# Power.net
KiCad netlist of a schematic drawn in Altium Designer
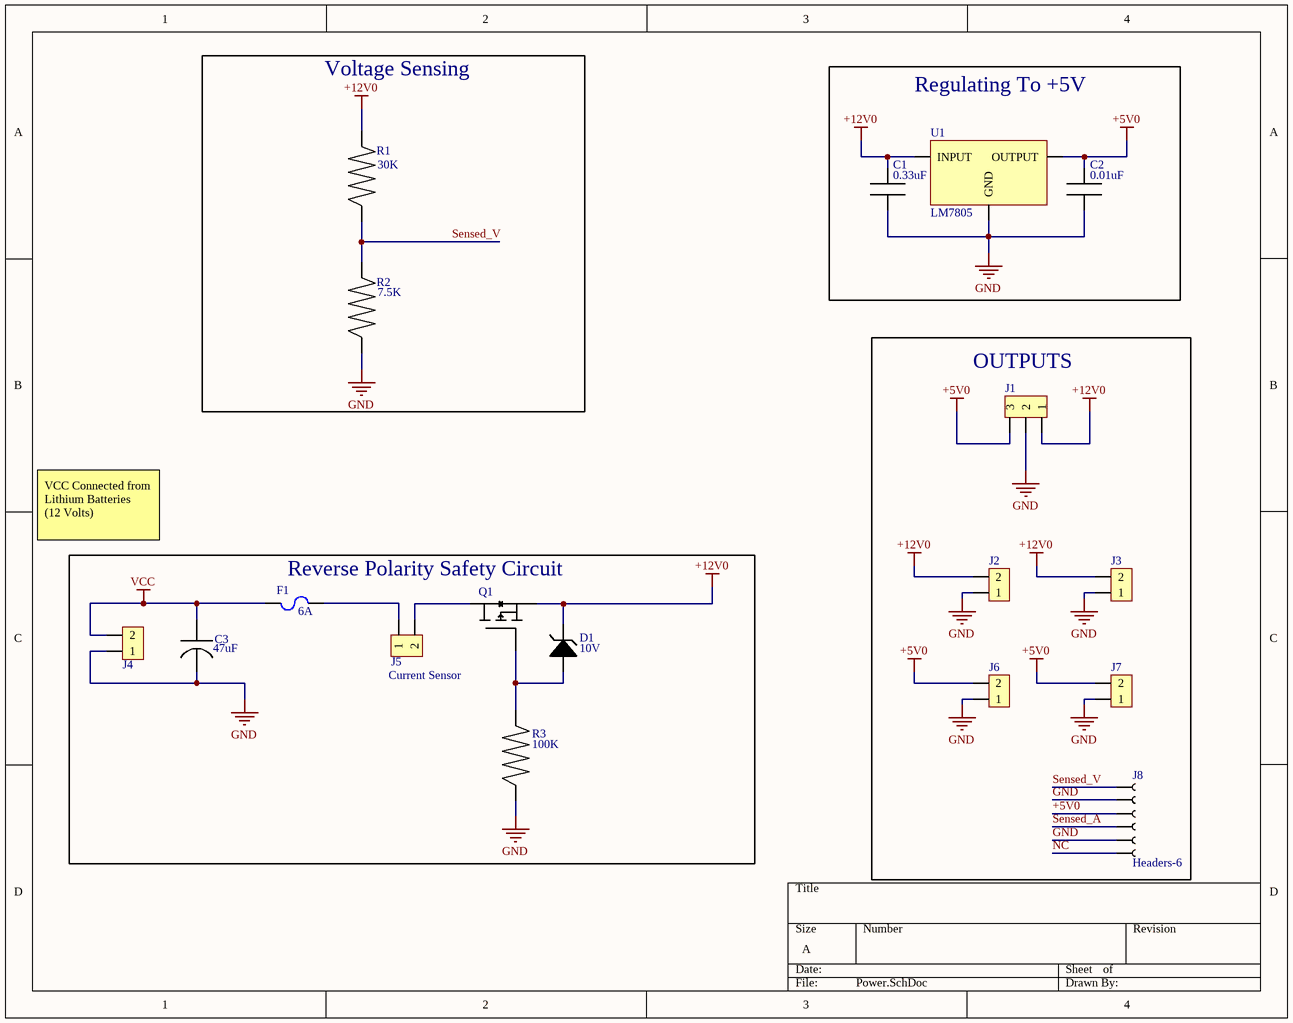
[diagram p0: Power.SchDoc]

(export (version "E")
  (design (tool "Eeschema 10.0.6"))
  (components
    (comp (ref "C1")
      (value "0.33uF")
      (footprint "Ceramic Cap")
      (fields (field (name "Comment") "Ceramic Capacitor"))
      (libsource (lib "Components") (part "Ceramic Capacitor"))
    )
    (comp (ref "C2")
      (value "0.01uF")
      (footprint "Ceramic Cap")
      (fields (field (name "Comment") "Ceramic Capacitor"))
      (libsource (lib "Components") (part "Ceramic Capacitor"))
    )
    (comp (ref "C3")
      (value "47uF")
      (footprint "ALCap.")
      (fields (field (name "Comment") "ALCapacitor"))
      (libsource (lib "Components") (part "ALCapacitor"))
    )
    (comp (ref "D1")
      (value "Zener")
      (footprint "Zener10")
      (fields (field (name "VD") "10V"))
      (libsource (lib "Components") (part "Zener"))
    )
    (comp (ref "F1")
      (value "6A")
      (footprint "Fuse Base")
      (fields (field (name "Comment") "Fuse"))
      (libsource (lib "Components") (part "Fuse"))
    )
    (comp (ref "J1")
      (value "Terminal Block 3")
      (footprint "Terminal Block 3")
      (libsource (lib "Components") (part "Terminal Block 3"))
    )
    (comp (ref "J2")
      (value "Terminal Block 2-pins")
      (footprint "Terminal Block 2 Plugable")
      (fields (field (name "MF") "Phoenix Contact"))
      (libsource (lib "Components") (part "Terminal Block 2-pins"))
    )
    (comp (ref "J3")
      (value "Terminal Block 2-pins")
      (footprint "Terminal Block 2 Plugable")
      (fields (field (name "MF") "Phoenix Contact"))
      (libsource (lib "Components") (part "Terminal Block 2-pins"))
    )
    (comp (ref "J4")
      (value "Terminal Block 2-pins")
      (footprint "Terminal Block 2 Plugable")
      (fields (field (name "MF") "Phoenix Contact"))
      (libsource (lib "Components") (part "Terminal Block 2-pins"))
    )
    (comp (ref "J5")
      (value "Current Sensor")
      (footprint "Terminal Block 2 Plugable")
      (fields (field (name "MF") "Phoenix Contact"))
      (libsource (lib "") (part "Terminal Block 2-pins_1"))
    )
    (comp (ref "J6")
      (value "Terminal Block 2-pins")
      (footprint "Terminal Block 2 Plugable")
      (fields (field (name "MF") "Phoenix Contact"))
      (libsource (lib "Components") (part "Terminal Block 2-pins"))
    )
    (comp (ref "J7")
      (value "Terminal Block 2-pins")
      (footprint "Terminal Block 2 Plugable")
      (fields (field (name "MF") "Phoenix Contact"))
      (libsource (lib "Components") (part "Terminal Block 2-pins"))
    )
    (comp (ref "J8")
      (value "Headers-6")
      (footprint "Headers 6-pins")
      (libsource (lib "Components") (part "Headers-6"))
    )
    (comp (ref "Q1")
      (value "MOSFET")
      (footprint "IRF9540")
      (description "P-Channel")
      (libsource (lib "Components") (part "MOSFET"))
    )
    (comp (ref "R1")
      (value "30K")
      (footprint "resistor")
      (fields (field (name "Comment") "Resistor"))
      (libsource (lib "Components") (part "Resistor"))
    )
    (comp (ref "R2")
      (value "7.5K")
      (footprint "resistor")
      (fields (field (name "Comment") "Resistor"))
      (libsource (lib "Components") (part "Resistor"))
    )
    (comp (ref "R3")
      (value "100K")
      (footprint "resistor")
      (fields (field (name "Comment") "Resistor"))
      (libsource (lib "Components") (part "Resistor"))
    )
    (comp (ref "U1") (value "LM7805") (footprint "LM7805") (libsource (lib "Components") (part "LM7805")))
  )
  (nets
    (net (code "1") (name "+5V0") (class "Default")
      (node (ref "C2") (pin "2") (pintype "passive"))
      (node (ref "J1") (pin "3") (pinfunction "3_3") (pintype "passive"))
      (node (ref "J6") (pin "2") (pinfunction "2_2") (pintype "passive"))
      (node (ref "J7") (pin "2") (pinfunction "2_2") (pintype "passive"))
      (node (ref "J8") (pin "4") (pintype "passive"))
      (node (ref "U1") (pin "3") (pinfunction "OUTPUT_3") (pintype "power_in"))
    )
    (net (code "2") (name "+12V0") (class "Default")
      (node (ref "C1") (pin "2") (pintype "passive"))
      (node (ref "D1") (pin "2") (pinfunction "Cath_2") (pintype "passive"))
      (node (ref "J1") (pin "1") (pinfunction "1_1") (pintype "passive"))
      (node (ref "J2") (pin "2") (pinfunction "2_2") (pintype "passive"))
      (node (ref "J3") (pin "2") (pinfunction "2_2") (pintype "passive"))
      (node (ref "Q1") (pin "S") (pinfunction "Source_S") (pintype "passive"))
      (node (ref "R1") (pin "2") (pinfunction "14_2") (pintype "passive"))
      (node (ref "U1") (pin "1") (pinfunction "INPUT_1") (pintype "power_in"))
    )
    (net (code "4") (name "/NC") (class "Default") (node (ref "J8") (pin "1") (pintype "passive")))
    (net (code "5") (name "/Sensed_A") (class "Default") (node (ref "J8") (pin "3") (pintype "passive")))
    (net (code "6") (name "/Sensed_V") (class "Default")
      (node (ref "J8") (pin "6") (pintype "passive"))
      (node (ref "R1") (pin "1") (pinfunction "13_1") (pintype "passive"))
      (node (ref "R2") (pin "2") (pinfunction "14_2") (pintype "passive"))
    )
    (net (code "7") (name "GND") (class "Default")
      (node (ref "C1") (pin "1") (pintype "passive"))
      (node (ref "C2") (pin "1") (pintype "passive"))
      (node (ref "C3") (pin "2") (pinfunction "4_2") (pintype "passive"))
      (node (ref "J1") (pin "2") (pinfunction "2_2") (pintype "passive"))
      (node (ref "J2") (pin "1") (pinfunction "1_1") (pintype "passive"))
      (node (ref "J3") (pin "1") (pinfunction "1_1") (pintype "passive"))
      (node (ref "J4") (pin "1") (pinfunction "1_1") (pintype "passive"))
      (node (ref "J6") (pin "1") (pinfunction "1_1") (pintype "passive"))
      (node (ref "J7") (pin "1") (pinfunction "1_1") (pintype "passive"))
      (node (ref "J8") (pin "2") (pintype "passive"))
      (node (ref "J8") (pin "5") (pintype "passive"))
      (node (ref "R2") (pin "1") (pinfunction "13_1") (pintype "passive"))
      (node (ref "R3") (pin "1") (pinfunction "13_1") (pintype "passive"))
      (node (ref "U1") (pin "2") (pinfunction "GND_2") (pintype "power_in"))
    )
    (net (code "8") (name "Net-(D1-anode)") (class "Default")
      (node (ref "D1") (pin "1") (pinfunction "anode_1") (pintype "passive"))
      (node (ref "Q1") (pin "G") (pinfunction "Gate_G") (pintype "passive"))
      (node (ref "R3") (pin "2") (pinfunction "14_2") (pintype "passive"))
    )
    (net (code "9") (name "Net-(F1-16)") (class "Default")
      (node (ref "F1") (pin "2") (pinfunction "16_2") (pintype "passive"))
      (node (ref "J5") (pin "1") (pinfunction "1_1") (pintype "passive"))
    )
    (net (code "10") (name "Net-(Q1-Drain)") (class "Default")
      (node (ref "J5") (pin "2") (pinfunction "2_2") (pintype "passive"))
      (node (ref "Q1") (pin "D") (pinfunction "Drain_D") (pintype "passive"))
    )
    (net (code "11") (name "VCC") (class "Default")
      (node (ref "C3") (pin "1") (pinfunction "5_1") (pintype "passive"))
      (node (ref "F1") (pin "1") (pinfunction "15_1") (pintype "passive"))
      (node (ref "J4") (pin "2") (pinfunction "2_2") (pintype "passive"))
    )
  )
)
